# ATmega1280.net
KiCad netlist of a schematic drawn in Altium Designer
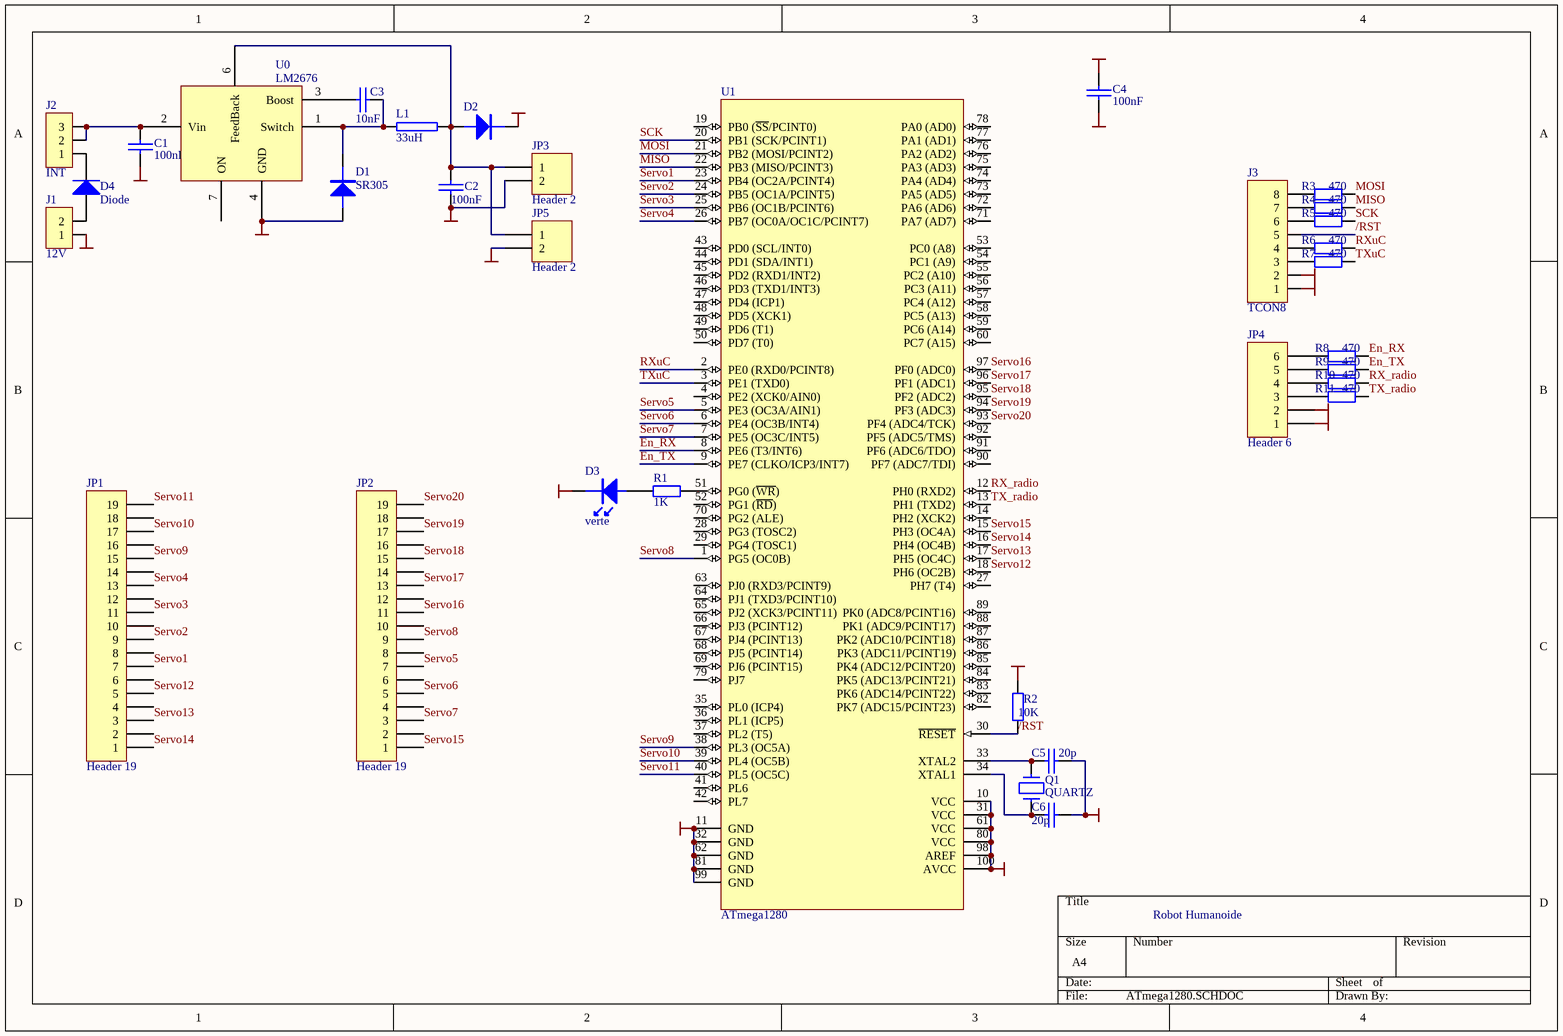
[diagram p0: ATmega1280.SCHDOC]

(export (version "E")
  (design (tool "Eeschema 10.0.6"))
  (components
    (comp (ref "C1") (value "100nF") (footprint "0805") (libsource (lib "*") (part "CAP")))
    (comp (ref "C2") (value "100nF") (footprint "0805") (libsource (lib "*") (part "CAP")))
    (comp (ref "C3") (value "10nF") (footprint "0805") (libsource (lib "*") (part "CONDO")))
    (comp (ref "C4") (value "100nF") (footprint "0805") (libsource (lib "*") (part "CAP")))
    (comp (ref "C5") (value "20p") (footprint "0805") (libsource (lib "*") (part "CONDO")))
    (comp (ref "C6") (value "20p") (footprint "0805") (libsource (lib "*") (part "CONDO")))
    (comp (ref "D1") (value "SR305") (footprint "1812") (libsource (lib "*") (part "DIODE")))
    (comp (ref "D2") (value "~") (footprint "1812") (libsource (lib "*") (part "DIODE")))
    (comp (ref "D3") (value "verte") (footprint "0603") (libsource (lib "*") (part "LED")))
    (comp (ref "D4")
      (value "Diode")
      (footprint "DSO-C2/X3.3")
      (description "Default Diode")
      (fields (field (name "PUBLISHER") "Altium Limited"))
      (libsource (lib "Miscellaneous Devices") (part "Diode"))
    )
    (comp (ref "J1") (value "12V") (footprint "CON2") (libsource (lib "*") (part "CON2")))
    (comp (ref "J2") (value "INT") (footprint "TSIP3") (libsource (lib "*") (part "TCON3")))
    (comp (ref "J3") (value "TCON8") (footprint "TSIP8") (libsource (lib "ROB04") (part "TCON8")))
    (comp (ref "JP1")
      (value "Header 19")
      (footprint "HDR1X19")
      (description "Header, 19-Pin")
      (fields (field (name "PUBLISHER") "Altium Limited"))
      (libsource (lib "Miscellaneous Connectors") (part "Header 19"))
    )
    (comp (ref "JP2")
      (value "Header 19")
      (footprint "HDR1X19")
      (description "Header, 19-Pin")
      (fields (field (name "PUBLISHER") "Altium Limited"))
      (libsource (lib "Miscellaneous Connectors") (part "Header 19"))
    )
    (comp (ref "JP3")
      (value "Header 2")
      (footprint "HDR1X2")
      (description "Header, 2-Pin")
      (fields (field (name "PUBLISHER") "Altium Limited"))
      (libsource (lib "Miscellaneous Connectors") (part "Header 2"))
    )
    (comp (ref "JP4")
      (value "Header 6")
      (footprint "TSIP6")
      (description "Header, 6-Pin")
      (fields (field (name "PUBLISHER") "Altium Limited"))
      (libsource (lib "Miscellaneous Connectors") (part "Header 6"))
    )
    (comp (ref "JP5")
      (value "Header 2")
      (footprint "HDR1X2")
      (description "Header, 2-Pin")
      (fields (field (name "PUBLISHER") "Altium Limited"))
      (libsource (lib "Miscellaneous Connectors") (part "Header 2"))
    )
    (comp (ref "L1")
      (value "33uH")
      (footprint "TRES")
      (fields (field (name "PUBLISHER") "*"))
      (libsource (lib "*") (part "RES2"))
    )
    (comp (ref "Q1") (value "QUARTZ") (footprint "XTAL1") (libsource (lib "*") (part "QUARTZ")))
    (comp (ref "R1")
      (value "1K")
      (footprint "0805")
      (description "Resistor")
      (fields (field (name "Comment") "Res2") (field (name "PUBLISHER") "Altium Limited"))
      (libsource (lib "Miscellaneous Devices") (part "Res2"))
    )
    (comp (ref "R2")
      (value "10K")
      (footprint "0805")
      (description "Resistor")
      (fields (field (name "Comment") "Res2") (field (name "PUBLISHER") "Altium Limited"))
      (libsource (lib "") (part "Res2_1"))
    )
    (comp (ref "R3")
      (value "470")
      (footprint "0805")
      (description "Resistor")
      (fields (field (name "Comment") "Res2") (field (name "PUBLISHER") "Altium Limited"))
      (libsource (lib "Miscellaneous Devices") (part "Res2"))
    )
    (comp (ref "R4")
      (value "470")
      (footprint "0805")
      (description "Resistor")
      (fields (field (name "Comment") "Res2") (field (name "PUBLISHER") "Altium Limited"))
      (libsource (lib "Miscellaneous Devices") (part "Res2"))
    )
    (comp (ref "R5")
      (value "470")
      (footprint "0805")
      (description "Resistor")
      (fields (field (name "Comment") "Res2") (field (name "PUBLISHER") "Altium Limited"))
      (libsource (lib "Miscellaneous Devices") (part "Res2"))
    )
    (comp (ref "R6")
      (value "470")
      (footprint "0805")
      (description "Resistor")
      (fields (field (name "Comment") "Res2") (field (name "PUBLISHER") "Altium Limited"))
      (libsource (lib "Miscellaneous Devices") (part "Res2"))
    )
    (comp (ref "R7")
      (value "470")
      (footprint "0805")
      (description "Resistor")
      (fields (field (name "Comment") "Res2") (field (name "PUBLISHER") "Altium Limited"))
      (libsource (lib "Miscellaneous Devices") (part "Res2"))
    )
    (comp (ref "R8")
      (value "470")
      (footprint "0805")
      (description "Resistor")
      (fields (field (name "Comment") "Res2") (field (name "PUBLISHER") "Altium Limited"))
      (libsource (lib "Miscellaneous Devices") (part "Res2"))
    )
    (comp (ref "R9")
      (value "470")
      (footprint "0805")
      (description "Resistor")
      (fields (field (name "Comment") "Res2") (field (name "PUBLISHER") "Altium Limited"))
      (libsource (lib "Miscellaneous Devices") (part "Res2"))
    )
    (comp (ref "R10")
      (value "470")
      (footprint "0805")
      (description "Resistor")
      (fields (field (name "Comment") "Res2") (field (name "PUBLISHER") "Altium Limited"))
      (libsource (lib "Miscellaneous Devices") (part "Res2"))
    )
    (comp (ref "R11")
      (value "470")
      (footprint "0805")
      (description "Resistor")
      (fields (field (name "Comment") "Res2") (field (name "PUBLISHER") "Altium Limited"))
      (libsource (lib "Miscellaneous Devices") (part "Res2"))
    )
    (comp (ref "U0") (value "LM2676") (footprint "LM2676") (libsource (lib "*") (part "LM2676")))
    (comp (ref "U1")
      (value "ATmega1280")
      (footprint "F-QFP14x14-G100/X.3N")
      (libsource (lib "lebomb") (part "ATmega1280"))
    )
  )
  (nets
    (net (code "1") (name "/En_RX") (class "Default")
      (node (ref "R8") (pin "2") (pinfunction "2_2") (pintype "passive"))
      (node (ref "U1") (pin "8") (pinfunction "PE6_(T3/INT6)_8") (pintype "bidirectional"))
    )
    (net (code "2") (name "/En_TX") (class "Default")
      (node (ref "R9") (pin "2") (pinfunction "2_2") (pintype "passive"))
      (node (ref "U1") (pin "9") (pinfunction "PE7_(CLKO/ICP3/INT7)_9") (pintype "bidirectional"))
    )
    (net (code "3") (name "/MISO") (class "Default")
      (node (ref "R4") (pin "2") (pinfunction "2_2") (pintype "passive"))
      (node (ref "U1") (pin "22") (pinfunction "PB3_(MISO/PCINT3)_22") (pintype "bidirectional"))
    )
    (net (code "4") (name "/MOSI") (class "Default")
      (node (ref "R3") (pin "2") (pinfunction "2_2") (pintype "passive"))
      (node (ref "U1") (pin "21") (pinfunction "PB2_(MOSI/PCINT2)_21") (pintype "bidirectional"))
    )
    (net (code "5") (name "/RX_radio") (class "Default")
      (node (ref "R10") (pin "2") (pinfunction "2_2") (pintype "passive"))
      (node (ref "U1") (pin "12") (pinfunction "PH0_(RXD2)_12") (pintype "bidirectional"))
    )
    (net (code "6") (name "/RXuC") (class "Default")
      (node (ref "R6") (pin "2") (pinfunction "2_2") (pintype "passive"))
      (node (ref "U1") (pin "2") (pinfunction "PE0_(RXD0/PCINT8)_2") (pintype "bidirectional"))
    )
    (net (code "7") (name "/SCK") (class "Default")
      (node (ref "R5") (pin "2") (pinfunction "2_2") (pintype "passive"))
      (node (ref "U1") (pin "20") (pinfunction "PB1_(SCK/PCINT1)_20") (pintype "bidirectional"))
    )
    (net (code "8") (name "/Servo1") (class "Default")
      (node (ref "JP1") (pin "7") (pinfunction "7_7") (pintype "passive"))
      (node (ref "U1") (pin "23") (pinfunction "PB4_(OC2A/PCINT4)_23") (pintype "bidirectional"))
    )
    (net (code "9") (name "/Servo2") (class "Default")
      (node (ref "JP1") (pin "9") (pinfunction "9_9") (pintype "passive"))
      (node (ref "U1") (pin "24") (pinfunction "PB5_(OC1A/PCINT5)_24") (pintype "bidirectional"))
    )
    (net (code "10") (name "/Servo3") (class "Default")
      (node (ref "JP1") (pin "11") (pinfunction "11_11") (pintype "passive"))
      (node (ref "U1") (pin "25") (pinfunction "PB6_(OC1B/PCINT6)_25") (pintype "bidirectional"))
    )
    (net (code "11") (name "/Servo4") (class "Default")
      (node (ref "JP1") (pin "13") (pinfunction "13_13") (pintype "passive"))
      (node (ref "U1") (pin "26") (pinfunction "PB7_(OC0A/OC1C/PCINT7)_26") (pintype "bidirectional"))
    )
    (net (code "12") (name "/Servo5") (class "Default")
      (node (ref "JP2") (pin "7") (pinfunction "7_7") (pintype "passive"))
      (node (ref "U1") (pin "5") (pinfunction "PE3_(OC3A/AIN1)_5") (pintype "bidirectional"))
    )
    (net (code "13") (name "/Servo6") (class "Default")
      (node (ref "JP2") (pin "5") (pinfunction "5_5") (pintype "passive"))
      (node (ref "U1") (pin "6") (pinfunction "PE4_(OC3B/INT4)_6") (pintype "bidirectional"))
    )
    (net (code "14") (name "/Servo7") (class "Default")
      (node (ref "JP2") (pin "3") (pinfunction "3_3") (pintype "passive"))
      (node (ref "U1") (pin "7") (pinfunction "PE5_(OC3C/INT5)_7") (pintype "bidirectional"))
    )
    (net (code "15") (name "/Servo8") (class "Default")
      (node (ref "JP2") (pin "9") (pinfunction "9_9") (pintype "passive"))
      (node (ref "U1") (pin "1") (pinfunction "PG5_(OC0B)_1") (pintype "bidirectional"))
    )
    (net (code "16") (name "/Servo9") (class "Default")
      (node (ref "JP1") (pin "15") (pinfunction "15_15") (pintype "passive"))
      (node (ref "U1") (pin "38") (pinfunction "PL3_(OC5A)_38") (pintype "bidirectional"))
    )
    (net (code "17") (name "/Servo10") (class "Default")
      (node (ref "JP1") (pin "17") (pinfunction "17_17") (pintype "passive"))
      (node (ref "U1") (pin "39") (pinfunction "PL4_(OC5B)_39") (pintype "bidirectional"))
    )
    (net (code "18") (name "/Servo11") (class "Default")
      (node (ref "JP1") (pin "19") (pinfunction "19_19") (pintype "passive"))
      (node (ref "U1") (pin "40") (pinfunction "PL5_(OC5C)_40") (pintype "bidirectional"))
    )
    (net (code "19") (name "/Servo12") (class "Default")
      (node (ref "JP1") (pin "5") (pinfunction "5_5") (pintype "passive"))
      (node (ref "U1") (pin "18") (pinfunction "PH6_(OC2B)_18") (pintype "bidirectional"))
    )
    (net (code "20") (name "/Servo13") (class "Default")
      (node (ref "JP1") (pin "3") (pinfunction "3_3") (pintype "passive"))
      (node (ref "U1") (pin "17") (pinfunction "PH5_(OC4C)_17") (pintype "bidirectional"))
    )
    (net (code "21") (name "/Servo14") (class "Default")
      (node (ref "JP1") (pin "1") (pinfunction "1_1") (pintype "passive"))
      (node (ref "U1") (pin "16") (pinfunction "PH4_(OC4B)_16") (pintype "bidirectional"))
    )
    (net (code "22") (name "/Servo15") (class "Default")
      (node (ref "JP2") (pin "1") (pinfunction "1_1") (pintype "passive"))
      (node (ref "U1") (pin "15") (pinfunction "PH3_(OC4A)_15") (pintype "bidirectional"))
    )
    (net (code "23") (name "/Servo16") (class "Default")
      (node (ref "JP2") (pin "11") (pinfunction "11_11") (pintype "passive"))
      (node (ref "U1") (pin "97") (pinfunction "PF0_(ADC0)_97") (pintype "bidirectional"))
    )
    (net (code "24") (name "/Servo17") (class "Default")
      (node (ref "JP2") (pin "13") (pinfunction "13_13") (pintype "passive"))
      (node (ref "U1") (pin "96") (pinfunction "PF1_(ADC1)_96") (pintype "bidirectional"))
    )
    (net (code "25") (name "/Servo18") (class "Default")
      (node (ref "JP2") (pin "15") (pinfunction "15_15") (pintype "passive"))
      (node (ref "U1") (pin "95") (pinfunction "PF2_(ADC2)_95") (pintype "bidirectional"))
    )
    (net (code "26") (name "/Servo19") (class "Default")
      (node (ref "JP2") (pin "17") (pinfunction "17_17") (pintype "passive"))
      (node (ref "U1") (pin "94") (pinfunction "PF3_(ADC3)_94") (pintype "bidirectional"))
    )
    (net (code "27") (name "/Servo20") (class "Default")
      (node (ref "JP2") (pin "19") (pinfunction "19_19") (pintype "passive"))
      (node (ref "U1") (pin "93") (pinfunction "PF4_(ADC4/TCK)_93") (pintype "bidirectional"))
    )
    (net (code "28") (name "/TX_radio") (class "Default")
      (node (ref "R11") (pin "2") (pinfunction "2_2") (pintype "passive"))
      (node (ref "U1") (pin "13") (pinfunction "PH1_(TXD2)_13") (pintype "bidirectional"))
    )
    (net (code "29") (name "/TXuC") (class "Default")
      (node (ref "R7") (pin "2") (pinfunction "2_2") (pintype "passive"))
      (node (ref "U1") (pin "3") (pinfunction "PE1_(TXD0)_3") (pintype "bidirectional"))
    )
    (net (code "30") (name "/{slash}RST") (class "Default")
      (node (ref "J3") (pin "5") (pinfunction "5_5") (pintype "passive"))
      (node (ref "R2") (pin "1") (pinfunction "1_1") (pintype "passive"))
      (node (ref "U1") (pin "30") (pinfunction "~{RESET}_30") (pintype "input"))
    )
    (net (code "31") (name "5V") (class "Default")
      (node (ref "C4") (pin "2") (pintype "passive"))
      (node (ref "D2") (pin "1") (pintype "passive"))
      (node (ref "J3") (pin "1") (pinfunction "1_1") (pintype "passive"))
      (node (ref "JP4") (pin "1") (pinfunction "1_1") (pintype "passive"))
      (node (ref "R2") (pin "2") (pinfunction "2_2") (pintype "passive"))
      (node (ref "U1") (pin "10") (pinfunction "VCC_10") (pintype "power_in"))
      (node (ref "U1") (pin "100") (pinfunction "AVCC_100") (pintype "power_in"))
      (node (ref "U1") (pin "31") (pinfunction "VCC_31") (pintype "power_in"))
      (node (ref "U1") (pin "61") (pinfunction "VCC_61") (pintype "power_in"))
      (node (ref "U1") (pin "80") (pinfunction "VCC_80") (pintype "power_in"))
      (node (ref "U1") (pin "98") (pinfunction "AREF_98") (pintype "passive"))
    )
    (net (code "32") (name "GND") (class "Default")
      (node (ref "C1") (pin "1") (pintype "passive"))
      (node (ref "C2") (pin "1") (pintype "passive"))
      (node (ref "C4") (pin "1") (pintype "passive"))
      (node (ref "C5") (pin "1") (pintype "passive"))
      (node (ref "C6") (pin "1") (pintype "passive"))
      (node (ref "D1") (pin "2") (pintype "passive"))
      (node (ref "D3") (pin "2") (pintype "passive"))
      (node (ref "J1") (pin "1") (pinfunction "1_1") (pintype "passive"))
      (node (ref "J3") (pin "2") (pinfunction "2_2") (pintype "passive"))
      (node (ref "JP3") (pin "2") (pinfunction "2_2") (pintype "passive"))
      (node (ref "JP4") (pin "2") (pinfunction "2_2") (pintype "passive"))
      (node (ref "JP5") (pin "2") (pinfunction "2_2") (pintype "passive"))
      (node (ref "U0") (pin "4") (pinfunction "GND_4") (pintype "passive"))
      (node (ref "U1") (pin "11") (pinfunction "GND_11") (pintype "power_in"))
      (node (ref "U1") (pin "32") (pinfunction "GND_32") (pintype "power_in"))
      (node (ref "U1") (pin "62") (pinfunction "GND_62") (pintype "power_in"))
      (node (ref "U1") (pin "81") (pinfunction "GND_81") (pintype "power_in"))
      (node (ref "U1") (pin "99") (pinfunction "GND_99") (pintype "power_in"))
    )
    (net (code "33") (name "Net-(D3-Pad1)") (class "Default")
      (node (ref "D3") (pin "1") (pintype "passive"))
      (node (ref "R1") (pin "1") (pinfunction "1_1") (pintype "passive"))
    )
    (net (code "34") (name "Net-(D4-A)") (class "Default")
      (node (ref "D4") (pin "1") (pinfunction "A_1") (pintype "passive"))
      (node (ref "J1") (pin "2") (pinfunction "2_2") (pintype "passive"))
    )
    (net (code "35") (name "Net-(D4-K)") (class "Default")
      (node (ref "D4") (pin "2") (pinfunction "K_2") (pintype "passive"))
      (node (ref "J2") (pin "1") (pinfunction "1_1") (pintype "passive"))
    )
    (net (code "36") (name "Net-(J3-Pad3)") (class "Default")
      (node (ref "J3") (pin "3") (pinfunction "3_3") (pintype "passive"))
      (node (ref "R7") (pin "1") (pinfunction "1_1") (pintype "passive"))
    )
    (net (code "37") (name "Net-(J3-Pad4)") (class "Default")
      (node (ref "J3") (pin "4") (pinfunction "4_4") (pintype "passive"))
      (node (ref "R6") (pin "1") (pinfunction "1_1") (pintype "passive"))
    )
    (net (code "38") (name "Net-(J3-Pad6)") (class "Default")
      (node (ref "J3") (pin "6") (pinfunction "6_6") (pintype "passive"))
      (node (ref "R5") (pin "1") (pinfunction "1_1") (pintype "passive"))
    )
    (net (code "39") (name "Net-(J3-Pad7)") (class "Default")
      (node (ref "J3") (pin "7") (pinfunction "7_7") (pintype "passive"))
      (node (ref "R4") (pin "1") (pinfunction "1_1") (pintype "passive"))
    )
    (net (code "40") (name "Net-(J3-Pad8)") (class "Default")
      (node (ref "J3") (pin "8") (pinfunction "8_8") (pintype "passive"))
      (node (ref "R3") (pin "1") (pinfunction "1_1") (pintype "passive"))
    )
    (net (code "41") (name "Net-(JP4-Pad3)") (class "Default")
      (node (ref "JP4") (pin "3") (pinfunction "3_3") (pintype "passive"))
      (node (ref "R11") (pin "1") (pinfunction "1_1") (pintype "passive"))
    )
    (net (code "42") (name "Net-(JP4-Pad4)") (class "Default")
      (node (ref "JP4") (pin "4") (pinfunction "4_4") (pintype "passive"))
      (node (ref "R10") (pin "1") (pinfunction "1_1") (pintype "passive"))
    )
    (net (code "43") (name "Net-(JP4-Pad5)") (class "Default")
      (node (ref "JP4") (pin "5") (pinfunction "5_5") (pintype "passive"))
      (node (ref "R9") (pin "1") (pinfunction "1_1") (pintype "passive"))
    )
    (net (code "44") (name "Net-(JP4-Pad6)") (class "Default")
      (node (ref "JP4") (pin "6") (pinfunction "6_6") (pintype "passive"))
      (node (ref "R8") (pin "1") (pinfunction "1_1") (pintype "passive"))
    )
    (net (code "45") (name "Net-(U0-Boost)") (class "Default")
      (node (ref "C3") (pin "1") (pintype "passive"))
      (node (ref "U0") (pin "3") (pinfunction "Boost_3") (pintype "passive"))
    )
    (net (code "46") (name "Net-(U0-FeedBack)") (class "Default")
      (node (ref "C2") (pin "2") (pintype "passive"))
      (node (ref "D2") (pin "2") (pintype "passive"))
      (node (ref "JP3") (pin "1") (pinfunction "1_1") (pintype "passive"))
      (node (ref "JP5") (pin "1") (pinfunction "1_1") (pintype "passive"))
      (node (ref "L1") (pin "2") (pintype "passive"))
      (node (ref "U0") (pin "6") (pinfunction "FeedBack_6") (pintype "passive"))
    )
    (net (code "47") (name "Net-(U0-Switch)") (class "Default")
      (node (ref "C3") (pin "2") (pintype "passive"))
      (node (ref "D1") (pin "1") (pintype "passive"))
      (node (ref "L1") (pin "1") (pintype "passive"))
      (node (ref "U0") (pin "1") (pinfunction "Switch_1") (pintype "passive"))
    )
    (net (code "48") (name "Net-(U0-Vin)") (class "Default")
      (node (ref "C1") (pin "2") (pintype "passive"))
      (node (ref "J2") (pin "2") (pinfunction "2_2") (pintype "passive"))
      (node (ref "J2") (pin "3") (pinfunction "3_3") (pintype "passive"))
      (node (ref "U0") (pin "2") (pinfunction "Vin_2") (pintype "passive"))
    )
    (net (code "49") (name "Net-(U1-PG0_(~{WR}))") (class "Default")
      (node (ref "R1") (pin "2") (pinfunction "2_2") (pintype "passive"))
      (node (ref "U1") (pin "51") (pinfunction "PG0_(~{WR})_51") (pintype "bidirectional"))
    )
    (net (code "50") (name "Net-(U1-XTAL1)") (class "Default")
      (node (ref "C6") (pin "2") (pintype "passive"))
      (node (ref "Q1") (pin "2") (pintype "passive"))
      (node (ref "U1") (pin "34") (pinfunction "XTAL1_34") (pintype "passive"))
    )
    (net (code "51") (name "Net-(U1-XTAL2)") (class "Default")
      (node (ref "C5") (pin "2") (pintype "passive"))
      (node (ref "Q1") (pin "1") (pintype "passive"))
      (node (ref "U1") (pin "33") (pinfunction "XTAL2_33") (pintype "passive"))
    )
    (net (code "52") (name "unconnected-(JP1-Pad2)") (class "Default")
      (node (ref "JP1") (pin "2") (pinfunction "2_2") (pintype "passive"))
    )
    (net (code "53") (name "unconnected-(JP1-Pad4)") (class "Default")
      (node (ref "JP1") (pin "4") (pinfunction "4_4") (pintype "passive"))
    )
    (net (code "54") (name "unconnected-(JP1-Pad6)") (class "Default")
      (node (ref "JP1") (pin "6") (pinfunction "6_6") (pintype "passive"))
    )
    (net (code "55") (name "unconnected-(JP1-Pad8)") (class "Default")
      (node (ref "JP1") (pin "8") (pinfunction "8_8") (pintype "passive"))
    )
    (net (code "56") (name "unconnected-(JP1-Pad10)") (class "Default")
      (node (ref "JP1") (pin "10") (pinfunction "10_10") (pintype "passive"))
    )
    (net (code "57") (name "unconnected-(JP1-Pad12)") (class "Default")
      (node (ref "JP1") (pin "12") (pinfunction "12_12") (pintype "passive"))
    )
    (net (code "58") (name "unconnected-(JP1-Pad14)") (class "Default")
      (node (ref "JP1") (pin "14") (pinfunction "14_14") (pintype "passive"))
    )
    (net (code "59") (name "unconnected-(JP1-Pad16)") (class "Default")
      (node (ref "JP1") (pin "16") (pinfunction "16_16") (pintype "passive"))
    )
    (net (code "60") (name "unconnected-(JP1-Pad18)") (class "Default")
      (node (ref "JP1") (pin "18") (pinfunction "18_18") (pintype "passive"))
    )
    (net (code "61") (name "unconnected-(JP2-Pad2)") (class "Default")
      (node (ref "JP2") (pin "2") (pinfunction "2_2") (pintype "passive"))
    )
    (net (code "62") (name "unconnected-(JP2-Pad4)") (class "Default")
      (node (ref "JP2") (pin "4") (pinfunction "4_4") (pintype "passive"))
    )
    (net (code "63") (name "unconnected-(JP2-Pad6)") (class "Default")
      (node (ref "JP2") (pin "6") (pinfunction "6_6") (pintype "passive"))
    )
    (net (code "64") (name "unconnected-(JP2-Pad8)") (class "Default")
      (node (ref "JP2") (pin "8") (pinfunction "8_8") (pintype "passive"))
    )
    (net (code "65") (name "unconnected-(JP2-Pad10)") (class "Default")
      (node (ref "JP2") (pin "10") (pinfunction "10_10") (pintype "passive"))
    )
    (net (code "66") (name "unconnected-(JP2-Pad12)") (class "Default")
      (node (ref "JP2") (pin "12") (pinfunction "12_12") (pintype "passive"))
    )
    (net (code "67") (name "unconnected-(JP2-Pad14)") (class "Default")
      (node (ref "JP2") (pin "14") (pinfunction "14_14") (pintype "passive"))
    )
    (net (code "68") (name "unconnected-(JP2-Pad16)") (class "Default")
      (node (ref "JP2") (pin "16") (pinfunction "16_16") (pintype "passive"))
    )
    (net (code "69") (name "unconnected-(JP2-Pad18)") (class "Default")
      (node (ref "JP2") (pin "18") (pinfunction "18_18") (pintype "passive"))
    )
    (net (code "70") (name "unconnected-(U0-ON-Pad7)") (class "Default")
      (node (ref "U0") (pin "7") (pinfunction "ON_7") (pintype "passive"))
    )
    (net (code "71") (name "unconnected-(U1-PA0_(AD0)-Pad78)") (class "Default")
      (node (ref "U1") (pin "78") (pinfunction "PA0_(AD0)_78") (pintype "bidirectional"))
    )
    (net (code "72") (name "unconnected-(U1-PA1_(AD1)-Pad77)") (class "Default")
      (node (ref "U1") (pin "77") (pinfunction "PA1_(AD1)_77") (pintype "bidirectional"))
    )
    (net (code "73") (name "unconnected-(U1-PA2_(AD2)-Pad76)") (class "Default")
      (node (ref "U1") (pin "76") (pinfunction "PA2_(AD2)_76") (pintype "bidirectional"))
    )
    (net (code "74") (name "unconnected-(U1-PA3_(AD3)-Pad75)") (class "Default")
      (node (ref "U1") (pin "75") (pinfunction "PA3_(AD3)_75") (pintype "bidirectional"))
    )
    (net (code "75") (name "unconnected-(U1-PA4_(AD4)-Pad74)") (class "Default")
      (node (ref "U1") (pin "74") (pinfunction "PA4_(AD4)_74") (pintype "bidirectional"))
    )
    (net (code "76") (name "unconnected-(U1-PA5_(AD5)-Pad73)") (class "Default")
      (node (ref "U1") (pin "73") (pinfunction "PA5_(AD5)_73") (pintype "bidirectional"))
    )
    (net (code "77") (name "unconnected-(U1-PA6_(AD6)-Pad72)") (class "Default")
      (node (ref "U1") (pin "72") (pinfunction "PA6_(AD6)_72") (pintype "bidirectional"))
    )
    (net (code "78") (name "unconnected-(U1-PA7_(AD7)-Pad71)") (class "Default")
      (node (ref "U1") (pin "71") (pinfunction "PA7_(AD7)_71") (pintype "bidirectional"))
    )
    (net (code "79") (name "unconnected-(U1-PB0_(~{SS}{slash}PCINT0)-Pad19)") (class "Default")
      (node (ref "U1") (pin "19") (pinfunction "PB0_(~{SS}/PCINT0)_19") (pintype "bidirectional"))
    )
    (net (code "80") (name "unconnected-(U1-PC0_(A8)-Pad53)") (class "Default")
      (node (ref "U1") (pin "53") (pinfunction "PC0_(A8)_53") (pintype "bidirectional"))
    )
    (net (code "81") (name "unconnected-(U1-PC1_(A9)-Pad54)") (class "Default")
      (node (ref "U1") (pin "54") (pinfunction "PC1_(A9)_54") (pintype "bidirectional"))
    )
    (net (code "82") (name "unconnected-(U1-PC2_(A10)-Pad55)") (class "Default")
      (node (ref "U1") (pin "55") (pinfunction "PC2_(A10)_55") (pintype "bidirectional"))
    )
    (net (code "83") (name "unconnected-(U1-PC3_(A11)-Pad56)") (class "Default")
      (node (ref "U1") (pin "56") (pinfunction "PC3_(A11)_56") (pintype "bidirectional"))
    )
    (net (code "84") (name "unconnected-(U1-PC4_(A12)-Pad57)") (class "Default")
      (node (ref "U1") (pin "57") (pinfunction "PC4_(A12)_57") (pintype "bidirectional"))
    )
    (net (code "85") (name "unconnected-(U1-PC5_(A13)-Pad58)") (class "Default")
      (node (ref "U1") (pin "58") (pinfunction "PC5_(A13)_58") (pintype "bidirectional"))
    )
    (net (code "86") (name "unconnected-(U1-PC6_(A14)-Pad59)") (class "Default")
      (node (ref "U1") (pin "59") (pinfunction "PC6_(A14)_59") (pintype "bidirectional"))
    )
    (net (code "87") (name "unconnected-(U1-PC7_(A15)-Pad60)") (class "Default")
      (node (ref "U1") (pin "60") (pinfunction "PC7_(A15)_60") (pintype "bidirectional"))
    )
    (net (code "88") (name "unconnected-(U1-PD0_(SCL{slash}INT0)-Pad43)") (class "Default")
      (node (ref "U1") (pin "43") (pinfunction "PD0_(SCL/INT0)_43") (pintype "bidirectional"))
    )
    (net (code "89") (name "unconnected-(U1-PD1_(SDA{slash}INT1)-Pad44)") (class "Default")
      (node (ref "U1") (pin "44") (pinfunction "PD1_(SDA/INT1)_44") (pintype "bidirectional"))
    )
    (net (code "90") (name "unconnected-(U1-PD2_(RXD1{slash}INT2)-Pad45)") (class "Default")
      (node (ref "U1") (pin "45") (pinfunction "PD2_(RXD1/INT2)_45") (pintype "bidirectional"))
    )
    (net (code "91") (name "unconnected-(U1-PD3_(TXD1{slash}INT3)-Pad46)") (class "Default")
      (node (ref "U1") (pin "46") (pinfunction "PD3_(TXD1/INT3)_46") (pintype "bidirectional"))
    )
    (net (code "92") (name "unconnected-(U1-PD4_(ICP1)-Pad47)") (class "Default")
      (node (ref "U1") (pin "47") (pinfunction "PD4_(ICP1)_47") (pintype "bidirectional"))
    )
    (net (code "93") (name "unconnected-(U1-PD5_(XCK1)-Pad48)") (class "Default")
      (node (ref "U1") (pin "48") (pinfunction "PD5_(XCK1)_48") (pintype "bidirectional"))
    )
    (net (code "94") (name "unconnected-(U1-PD6_(T1)-Pad49)") (class "Default")
      (node (ref "U1") (pin "49") (pinfunction "PD6_(T1)_49") (pintype "bidirectional"))
    )
    (net (code "95") (name "unconnected-(U1-PD7_(T0)-Pad50)") (class "Default")
      (node (ref "U1") (pin "50") (pinfunction "PD7_(T0)_50") (pintype "bidirectional"))
    )
    (net (code "96") (name "unconnected-(U1-PE2_(XCK0{slash}AIN0)-Pad4)") (class "Default")
      (node (ref "U1") (pin "4") (pinfunction "PE2_(XCK0/AIN0)_4") (pintype "bidirectional"))
    )
    (net (code "97") (name "unconnected-(U1-PF5_(ADC5{slash}TMS)-Pad92)") (class "Default")
      (node (ref "U1") (pin "92") (pinfunction "PF5_(ADC5/TMS)_92") (pintype "bidirectional"))
    )
    (net (code "98") (name "unconnected-(U1-PF6_(ADC6{slash}TDO)-Pad91)") (class "Default")
      (node (ref "U1") (pin "91") (pinfunction "PF6_(ADC6/TDO)_91") (pintype "bidirectional"))
    )
    (net (code "99") (name "unconnected-(U1-PF7_(ADC7{slash}TDI)-Pad90)") (class "Default")
      (node (ref "U1") (pin "90") (pinfunction "PF7_(ADC7/TDI)_90") (pintype "bidirectional"))
    )
    (net (code "100") (name "unconnected-(U1-PG1_(~{RD})-Pad52)") (class "Default")
      (node (ref "U1") (pin "52") (pinfunction "PG1_(~{RD})_52") (pintype "bidirectional"))
    )
    (net (code "101") (name "unconnected-(U1-PG2_(ALE)-Pad70)") (class "Default")
      (node (ref "U1") (pin "70") (pinfunction "PG2_(ALE)_70") (pintype "bidirectional"))
    )
    (net (code "102") (name "unconnected-(U1-PG3_(TOSC2)-Pad28)") (class "Default")
      (node (ref "U1") (pin "28") (pinfunction "PG3_(TOSC2)_28") (pintype "bidirectional"))
    )
    (net (code "103") (name "unconnected-(U1-PG4_(TOSC1)-Pad29)") (class "Default")
      (node (ref "U1") (pin "29") (pinfunction "PG4_(TOSC1)_29") (pintype "bidirectional"))
    )
    (net (code "104") (name "unconnected-(U1-PH2_(XCK2)-Pad14)") (class "Default")
      (node (ref "U1") (pin "14") (pinfunction "PH2_(XCK2)_14") (pintype "bidirectional"))
    )
    (net (code "105") (name "unconnected-(U1-PH7_(T4)-Pad27)") (class "Default")
      (node (ref "U1") (pin "27") (pinfunction "PH7_(T4)_27") (pintype "bidirectional"))
    )
    (net (code "106") (name "unconnected-(U1-PJ0_(RXD3{slash}PCINT9)-Pad63)") (class "Default")
      (node (ref "U1") (pin "63") (pinfunction "PJ0_(RXD3/PCINT9)_63") (pintype "bidirectional"))
    )
    (net (code "107") (name "unconnected-(U1-PJ1_(TXD3{slash}PCINT10)-Pad64)") (class "Default")
      (node (ref "U1") (pin "64") (pinfunction "PJ1_(TXD3/PCINT10)_64") (pintype "bidirectional"))
    )
    (net (code "108") (name "unconnected-(U1-PJ2_(XCK3{slash}PCINT11)-Pad65)") (class "Default")
      (node (ref "U1") (pin "65") (pinfunction "PJ2_(XCK3/PCINT11)_65") (pintype "bidirectional"))
    )
    (net (code "109") (name "unconnected-(U1-PJ3_(PCINT12)-Pad66)") (class "Default")
      (node (ref "U1") (pin "66") (pinfunction "PJ3_(PCINT12)_66") (pintype "bidirectional"))
    )
    (net (code "110") (name "unconnected-(U1-PJ4_(PCINT13)-Pad67)") (class "Default")
      (node (ref "U1") (pin "67") (pinfunction "PJ4_(PCINT13)_67") (pintype "bidirectional"))
    )
    (net (code "111") (name "unconnected-(U1-PJ5_(PCINT14)-Pad68)") (class "Default")
      (node (ref "U1") (pin "68") (pinfunction "PJ5_(PCINT14)_68") (pintype "bidirectional"))
    )
    (net (code "112") (name "unconnected-(U1-PJ6_(PCINT15)-Pad69)") (class "Default")
      (node (ref "U1") (pin "69") (pinfunction "PJ6_(PCINT15)_69") (pintype "bidirectional"))
    )
    (net (code "113") (name "unconnected-(U1-PJ7-Pad79)") (class "Default")
      (node (ref "U1") (pin "79") (pinfunction "PJ7_79") (pintype "bidirectional"))
    )
    (net (code "114") (name "unconnected-(U1-PK0_(ADC8{slash}PCINT16)-Pad89)") (class "Default")
      (node (ref "U1") (pin "89") (pinfunction "PK0_(ADC8/PCINT16)_89") (pintype "bidirectional"))
    )
    (net (code "115") (name "unconnected-(U1-PK1_(ADC9{slash}PCINT17)-Pad88)") (class "Default")
      (node (ref "U1") (pin "88") (pinfunction "PK1_(ADC9/PCINT17)_88") (pintype "bidirectional"))
    )
    (net (code "116") (name "unconnected-(U1-PK2_(ADC10{slash}PCINT18)-Pad87)") (class "Default")
      (node (ref "U1") (pin "87") (pinfunction "PK2_(ADC10/PCINT18)_87") (pintype "bidirectional"))
    )
    (net (code "117") (name "unconnected-(U1-PK3_(ADC11{slash}PCINT19)-Pad86)") (class "Default")
      (node (ref "U1") (pin "86") (pinfunction "PK3_(ADC11/PCINT19)_86") (pintype "bidirectional"))
    )
    (net (code "118") (name "unconnected-(U1-PK4_(ADC12{slash}PCINT20)-Pad85)") (class "Default")
      (node (ref "U1") (pin "85") (pinfunction "PK4_(ADC12/PCINT20)_85") (pintype "bidirectional"))
    )
    (net (code "119") (name "unconnected-(U1-PK5_(ADC13{slash}PCINT21)-Pad84)") (class "Default")
      (node (ref "U1") (pin "84") (pinfunction "PK5_(ADC13/PCINT21)_84") (pintype "bidirectional"))
    )
    (net (code "120") (name "unconnected-(U1-PK6_(ADC14{slash}PCINT22)-Pad83)") (class "Default")
      (node (ref "U1") (pin "83") (pinfunction "PK6_(ADC14/PCINT22)_83") (pintype "bidirectional"))
    )
    (net (code "121") (name "unconnected-(U1-PK7_(ADC15{slash}PCINT23)-Pad82)") (class "Default")
      (node (ref "U1") (pin "82") (pinfunction "PK7_(ADC15/PCINT23)_82") (pintype "bidirectional"))
    )
    (net (code "122") (name "unconnected-(U1-PL0_(ICP4)-Pad35)") (class "Default")
      (node (ref "U1") (pin "35") (pinfunction "PL0_(ICP4)_35") (pintype "bidirectional"))
    )
    (net (code "123") (name "unconnected-(U1-PL1_(ICP5)-Pad36)") (class "Default")
      (node (ref "U1") (pin "36") (pinfunction "PL1_(ICP5)_36") (pintype "bidirectional"))
    )
    (net (code "124") (name "unconnected-(U1-PL2_(T5)-Pad37)") (class "Default")
      (node (ref "U1") (pin "37") (pinfunction "PL2_(T5)_37") (pintype "bidirectional"))
    )
    (net (code "125") (name "unconnected-(U1-PL6-Pad41)") (class "Default")
      (node (ref "U1") (pin "41") (pinfunction "PL6_41") (pintype "bidirectional"))
    )
    (net (code "126") (name "unconnected-(U1-PL7-Pad42)") (class "Default")
      (node (ref "U1") (pin "42") (pinfunction "PL7_42") (pintype "bidirectional"))
    )
  )
)
